# attenuator.net
KiCad netlist of a schematic drawn in EAGLE
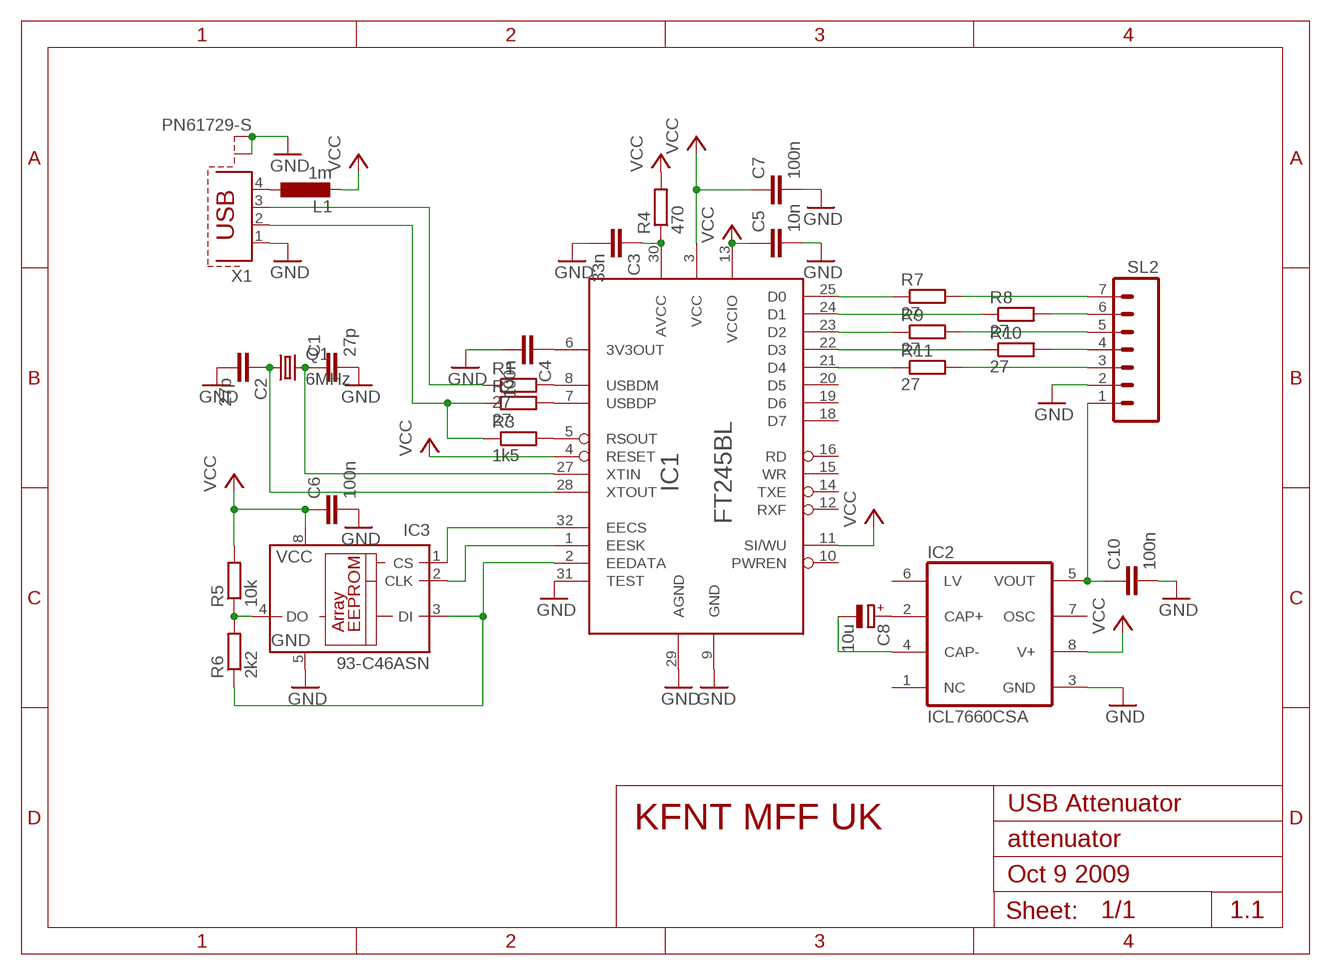
[diagram p0: schematic, sheet 1]

(export (version "E")
  (design (tool "Eeschema 10.0.6"))
  (components
    (comp (ref "C1")
      (value "27p")
      (footprint "eagle-import:C0805")
      (libsource (lib "eagle-import") (part "C-EUC0805"))
    )
    (comp (ref "C2")
      (value "27p")
      (footprint "eagle-import:C0805")
      (libsource (lib "eagle-import") (part "C-EUC0805"))
    )
    (comp (ref "C3")
      (value "33n")
      (footprint "eagle-import:C0805")
      (libsource (lib "eagle-import") (part "C-EUC0805"))
    )
    (comp (ref "C4")
      (value "100n")
      (footprint "eagle-import:C0805")
      (libsource (lib "eagle-import") (part "C-EUC0805"))
    )
    (comp (ref "C5")
      (value "10n")
      (footprint "eagle-import:C0805")
      (libsource (lib "eagle-import") (part "C-EUC0805"))
    )
    (comp (ref "C6")
      (value "100n")
      (footprint "eagle-import:C0805")
      (libsource (lib "eagle-import") (part "C-EUC0805"))
    )
    (comp (ref "C7")
      (value "100n")
      (footprint "eagle-import:C0805")
      (libsource (lib "eagle-import") (part "C-EUC0805"))
    )
    (comp (ref "C8")
      (value "10u")
      (footprint "eagle-import:SMC_C")
      (libsource (lib "eagle-import") (part "CPOL-EUSMCC"))
    )
    (comp (ref "C10")
      (value "100n")
      (footprint "eagle-import:C0805")
      (libsource (lib "eagle-import") (part "C-EUC0805"))
    )
    (comp (ref "IC1")
      (value "FT245BL")
      (footprint "eagle-import:LQFP32")
      (libsource (lib "eagle-import") (part "FT245BL"))
    )
    (comp (ref "IC2")
      (value "ICL7660CSA")
      (footprint "eagle-import:SO08")
      (libsource (lib "eagle-import") (part "ICL7660CSA"))
    )
    (comp (ref "IC3")
      (value "93-C46ASN")
      (footprint "eagle-import:SO-08")
      (libsource (lib "eagle-import") (part "93-SNC46A"))
    )
    (comp (ref "L1")
      (value "1m")
      (footprint "eagle-import:M0805")
      (libsource (lib "eagle-import") (part "L-EU0805"))
    )
    (comp (ref "Q1")
      (value "6MHz")
      (footprint "eagle-import:HC49U70")
      (libsource (lib "eagle-import") (part "CRYSTALHC49U70"))
    )
    (comp (ref "R1")
      (value "27")
      (footprint "eagle-import:M0805")
      (libsource (lib "eagle-import") (part "R-EU_M0805"))
    )
    (comp (ref "R2")
      (value "27")
      (footprint "eagle-import:M0805")
      (libsource (lib "eagle-import") (part "R-EU_M0805"))
    )
    (comp (ref "R3")
      (value "1k5")
      (footprint "eagle-import:M0805")
      (libsource (lib "eagle-import") (part "R-EU_M0805"))
    )
    (comp (ref "R4")
      (value "470")
      (footprint "eagle-import:M0805")
      (libsource (lib "eagle-import") (part "R-EU_M0805"))
    )
    (comp (ref "R5")
      (value "10k")
      (footprint "eagle-import:M0805")
      (libsource (lib "eagle-import") (part "R-EU_M0805"))
    )
    (comp (ref "R6")
      (value "2k2")
      (footprint "eagle-import:M0805")
      (libsource (lib "eagle-import") (part "R-EU_M0805"))
    )
    (comp (ref "R7")
      (value "27")
      (footprint "eagle-import:M0805")
      (libsource (lib "eagle-import") (part "R-EU_M0805"))
    )
    (comp (ref "R8")
      (value "27")
      (footprint "eagle-import:M0805")
      (libsource (lib "eagle-import") (part "R-EU_M0805"))
    )
    (comp (ref "R9")
      (value "27")
      (footprint "eagle-import:M0805")
      (libsource (lib "eagle-import") (part "R-EU_M0805"))
    )
    (comp (ref "R10")
      (value "27")
      (footprint "eagle-import:M0805")
      (libsource (lib "eagle-import") (part "R-EU_M0805"))
    )
    (comp (ref "R11")
      (value "27")
      (footprint "eagle-import:M0805")
      (libsource (lib "eagle-import") (part "R-EU_M0805"))
    )
    (comp (ref "SL2")
      (value "MA07")
      (footprint "eagle-import:07PA")
      (libsource (lib "eagle-import") (part "MA07"))
    )
    (comp (ref "X1")
      (value "PN61729-S")
      (footprint "eagle-import:PN61729-S")
      (libsource (lib "eagle-import") (part "PN61729-S"))
    )
  )
  (nets
    (net (code "1") (name "GND") (class "Default")
      (node (ref "C1") (pin "2") (pinfunction "2_2") (pintype "passive"))
      (node (ref "C10") (pin "2") (pinfunction "2_2") (pintype "passive"))
      (node (ref "C2") (pin "2") (pinfunction "2_2") (pintype "passive"))
      (node (ref "C3") (pin "2") (pinfunction "2_2") (pintype "passive"))
      (node (ref "C4") (pin "2") (pinfunction "2_2") (pintype "passive"))
      (node (ref "C5") (pin "2") (pinfunction "2_2") (pintype "passive"))
      (node (ref "C6") (pin "2") (pinfunction "2_2") (pintype "passive"))
      (node (ref "C7") (pin "2") (pinfunction "2_2") (pintype "passive"))
      (node (ref "IC1") (pin "29") (pinfunction "AGND_29") (pintype "power_in"))
      (node (ref "IC1") (pin "31") (pinfunction "TEST_31") (pintype "bidirectional"))
      (node (ref "IC1") (pin "9") (pinfunction "GND_9") (pintype "power_in"))
      (node (ref "IC2") (pin "3") (pinfunction "GND_3") (pintype "power_in"))
      (node (ref "IC3") (pin "5") (pinfunction "GND_5") (pintype "power_in"))
      (node (ref "SL2") (pin "2") (pinfunction "2_2") (pintype "passive"))
      (node (ref "X1") (pin "1") (pinfunction "1_1") (pintype "passive"))
      (node (ref "X1") (pin "S1") (pinfunction "S1_S1") (pintype "passive"))
      (node (ref "X1") (pin "S2") (pinfunction "S2_S2") (pintype "passive"))
    )
    (net (code "2") (name "Net-(IC1A-3V3OUT)") (class "Default")
      (node (ref "C4") (pin "1") (pinfunction "1_1") (pintype "passive"))
      (node (ref "IC1") (pin "6") (pinfunction "3V3OUT_6") (pintype "bidirectional"))
    )
    (net (code "3") (name "Net-(IC1A-AVCC)") (class "Default")
      (node (ref "C3") (pin "1") (pinfunction "1_1") (pintype "passive"))
      (node (ref "IC1") (pin "30") (pinfunction "AVCC_30") (pintype "power_in"))
      (node (ref "R4") (pin "1") (pinfunction "1_1") (pintype "passive"))
    )
    (net (code "4") (name "Net-(IC1A-D0)") (class "Default")
      (node (ref "IC1") (pin "25") (pinfunction "D0_25") (pintype "bidirectional"))
      (node (ref "R7") (pin "1") (pinfunction "1_1") (pintype "passive"))
    )
    (net (code "5") (name "Net-(IC1A-D1)") (class "Default")
      (node (ref "IC1") (pin "24") (pinfunction "D1_24") (pintype "bidirectional"))
      (node (ref "R8") (pin "1") (pinfunction "1_1") (pintype "passive"))
    )
    (net (code "6") (name "Net-(IC1A-D2)") (class "Default")
      (node (ref "IC1") (pin "23") (pinfunction "D2_23") (pintype "bidirectional"))
      (node (ref "R9") (pin "1") (pinfunction "1_1") (pintype "passive"))
    )
    (net (code "7") (name "Net-(IC1A-D3)") (class "Default")
      (node (ref "IC1") (pin "22") (pinfunction "D3_22") (pintype "bidirectional"))
      (node (ref "R10") (pin "1") (pinfunction "1_1") (pintype "passive"))
    )
    (net (code "8") (name "Net-(IC1A-D4)") (class "Default")
      (node (ref "IC1") (pin "21") (pinfunction "D4_21") (pintype "bidirectional"))
      (node (ref "R11") (pin "1") (pinfunction "1_1") (pintype "passive"))
    )
    (net (code "9") (name "Net-(IC1A-EECS)") (class "Default")
      (node (ref "IC1") (pin "32") (pinfunction "EECS_32") (pintype "bidirectional"))
      (node (ref "IC3") (pin "1") (pinfunction "CS_1") (pintype "input"))
    )
    (net (code "10") (name "Net-(IC1A-EEDATA)") (class "Default")
      (node (ref "IC1") (pin "2") (pinfunction "EEDATA_2") (pintype "bidirectional"))
      (node (ref "IC3") (pin "3") (pinfunction "DI_3") (pintype "input"))
      (node (ref "R6") (pin "1") (pinfunction "1_1") (pintype "passive"))
    )
    (net (code "11") (name "Net-(IC1A-EESK)") (class "Default")
      (node (ref "IC1") (pin "1") (pinfunction "EESK_1") (pintype "bidirectional"))
      (node (ref "IC3") (pin "2") (pinfunction "CLK_2") (pintype "input"))
    )
    (net (code "12") (name "Net-(IC1A-RSOUT)") (class "Default")
      (node (ref "IC1") (pin "5") (pinfunction "RSOUT_5") (pintype "power_in"))
      (node (ref "R3") (pin "2") (pinfunction "2_2") (pintype "passive"))
    )
    (net (code "13") (name "Net-(IC1A-USBDM)") (class "Default")
      (node (ref "IC1") (pin "8") (pinfunction "USBDM_8") (pintype "bidirectional"))
      (node (ref "R1") (pin "2") (pinfunction "2_2") (pintype "passive"))
    )
    (net (code "14") (name "Net-(IC1A-USBDP)") (class "Default")
      (node (ref "IC1") (pin "7") (pinfunction "USBDP_7") (pintype "bidirectional"))
      (node (ref "R2") (pin "2") (pinfunction "2_2") (pintype "passive"))
    )
    (net (code "15") (name "Net-(IC1A-XTIN)") (class "Default")
      (node (ref "C1") (pin "1") (pinfunction "1_1") (pintype "passive"))
      (node (ref "IC1") (pin "27") (pinfunction "XTIN_27") (pintype "bidirectional"))
      (node (ref "Q1") (pin "2") (pinfunction "2_2") (pintype "passive"))
    )
    (net (code "16") (name "Net-(IC1A-XTOUT)") (class "Default")
      (node (ref "C2") (pin "1") (pinfunction "1_1") (pintype "passive"))
      (node (ref "IC1") (pin "28") (pinfunction "XTOUT_28") (pintype "bidirectional"))
      (node (ref "Q1") (pin "1") (pinfunction "1_1") (pintype "passive"))
    )
    (net (code "17") (name "Net-(IC2-CAP+)") (class "Default")
      (node (ref "C8") (pin "+") (pinfunction "+_+") (pintype "passive"))
      (node (ref "IC2") (pin "2") (pinfunction "CAP+_2") (pintype "passive"))
    )
    (net (code "18") (name "Net-(IC2-CAP-)") (class "Default")
      (node (ref "C8") (pin "-") (pinfunction "-_-") (pintype "passive"))
      (node (ref "IC2") (pin "4") (pinfunction "CAP-_4") (pintype "passive"))
    )
    (net (code "19") (name "Net-(IC2-VOUT)") (class "Default")
      (node (ref "C10") (pin "1") (pinfunction "1_1") (pintype "passive"))
      (node (ref "IC2") (pin "5") (pinfunction "VOUT_5") (pintype "output"))
      (node (ref "SL2") (pin "1") (pinfunction "1_1") (pintype "passive"))
    )
    (net (code "20") (name "Net-(IC3-DO)") (class "Default")
      (node (ref "IC3") (pin "4") (pinfunction "DO_4") (pintype "tri_state"))
      (node (ref "R5") (pin "1") (pinfunction "1_1") (pintype "passive"))
      (node (ref "R6") (pin "2") (pinfunction "2_2") (pintype "passive"))
    )
    (net (code "21") (name "Net-(L1-Pad1)") (class "Default")
      (node (ref "L1") (pin "1") (pinfunction "1_1") (pintype "passive"))
      (node (ref "X1") (pin "4") (pinfunction "4_4") (pintype "passive"))
    )
    (net (code "22") (name "Net-(R1-Pad1)") (class "Default")
      (node (ref "R1") (pin "1") (pinfunction "1_1") (pintype "passive"))
      (node (ref "X1") (pin "3") (pinfunction "3_3") (pintype "passive"))
    )
    (net (code "23") (name "Net-(R2-Pad1)") (class "Default")
      (node (ref "R2") (pin "1") (pinfunction "1_1") (pintype "passive"))
      (node (ref "R3") (pin "1") (pinfunction "1_1") (pintype "passive"))
      (node (ref "X1") (pin "2") (pinfunction "2_2") (pintype "passive"))
    )
    (net (code "24") (name "Net-(R7-Pad2)") (class "Default")
      (node (ref "R7") (pin "2") (pinfunction "2_2") (pintype "passive"))
      (node (ref "SL2") (pin "7") (pinfunction "7_7") (pintype "passive"))
    )
    (net (code "25") (name "Net-(R8-Pad2)") (class "Default")
      (node (ref "R8") (pin "2") (pinfunction "2_2") (pintype "passive"))
      (node (ref "SL2") (pin "6") (pinfunction "6_6") (pintype "passive"))
    )
    (net (code "26") (name "Net-(R9-Pad2)") (class "Default")
      (node (ref "R9") (pin "2") (pinfunction "2_2") (pintype "passive"))
      (node (ref "SL2") (pin "5") (pinfunction "5_5") (pintype "passive"))
    )
    (net (code "27") (name "Net-(R10-Pad2)") (class "Default")
      (node (ref "R10") (pin "2") (pinfunction "2_2") (pintype "passive"))
      (node (ref "SL2") (pin "4") (pinfunction "4_4") (pintype "passive"))
    )
    (net (code "28") (name "Net-(R11-Pad2)") (class "Default")
      (node (ref "R11") (pin "2") (pinfunction "2_2") (pintype "passive"))
      (node (ref "SL2") (pin "3") (pinfunction "3_3") (pintype "passive"))
    )
    (net (code "29") (name "VCC") (class "Default")
      (node (ref "C5") (pin "1") (pinfunction "1_1") (pintype "passive"))
      (node (ref "C6") (pin "1") (pinfunction "1_1") (pintype "passive"))
      (node (ref "C7") (pin "1") (pinfunction "1_1") (pintype "passive"))
      (node (ref "IC1") (pin "11") (pinfunction "SI/WU_11") (pintype "bidirectional"))
      (node (ref "IC1") (pin "13") (pinfunction "VCCIO_13") (pintype "bidirectional"))
      (node (ref "IC1") (pin "3") (pinfunction "VCC_3") (pintype "power_in"))
      (node (ref "IC1") (pin "4") (pinfunction "RESET_4") (pintype "bidirectional"))
      (node (ref "IC2") (pin "8") (pinfunction "V+_8") (pintype "power_in"))
      (node (ref "IC3") (pin "8") (pinfunction "VCC_8") (pintype "power_in"))
      (node (ref "L1") (pin "2") (pinfunction "2_2") (pintype "passive"))
      (node (ref "R4") (pin "2") (pinfunction "2_2") (pintype "passive"))
      (node (ref "R5") (pin "2") (pinfunction "2_2") (pintype "passive"))
    )
    (net (code "30") (name "unconnected-(IC1A-D5-Pad20)") (class "Default")
      (node (ref "IC1") (pin "20") (pinfunction "D5_20") (pintype "bidirectional"))
    )
    (net (code "31") (name "unconnected-(IC1A-D6-Pad19)") (class "Default")
      (node (ref "IC1") (pin "19") (pinfunction "D6_19") (pintype "bidirectional"))
    )
    (net (code "32") (name "unconnected-(IC1A-D7-Pad18)") (class "Default")
      (node (ref "IC1") (pin "18") (pinfunction "D7_18") (pintype "bidirectional"))
    )
    (net (code "33") (name "unconnected-(IC1A-PWREN-Pad10)") (class "Default")
      (node (ref "IC1") (pin "10") (pinfunction "PWREN_10") (pintype "bidirectional"))
    )
    (net (code "34") (name "unconnected-(IC1A-RD-Pad16)") (class "Default")
      (node (ref "IC1") (pin "16") (pinfunction "RD_16") (pintype "bidirectional"))
    )
    (net (code "35") (name "unconnected-(IC1A-RXF-Pad12)") (class "Default")
      (node (ref "IC1") (pin "12") (pinfunction "RXF_12") (pintype "bidirectional"))
    )
    (net (code "36") (name "unconnected-(IC1A-TXE-Pad14)") (class "Default")
      (node (ref "IC1") (pin "14") (pinfunction "TXE_14") (pintype "bidirectional"))
    )
    (net (code "37") (name "unconnected-(IC1A-WR-Pad15)") (class "Default")
      (node (ref "IC1") (pin "15") (pinfunction "WR_15") (pintype "bidirectional"))
    )
    (net (code "38") (name "unconnected-(IC2-LV-Pad6)") (class "Default")
      (node (ref "IC2") (pin "6") (pinfunction "LV_6") (pintype "passive"))
    )
    (net (code "39") (name "unconnected-(IC2-NC-Pad1)") (class "Default")
      (node (ref "IC2") (pin "1") (pinfunction "NC_1") (pintype "no_connect"))
    )
    (net (code "40") (name "unconnected-(IC2-OSC-Pad7)") (class "Default")
      (node (ref "IC2") (pin "7") (pinfunction "OSC_7") (pintype "output"))
    )
  )
)
